# Three_Phase_Inverter.net
KiCad netlist of a schematic drawn in Altium Designer
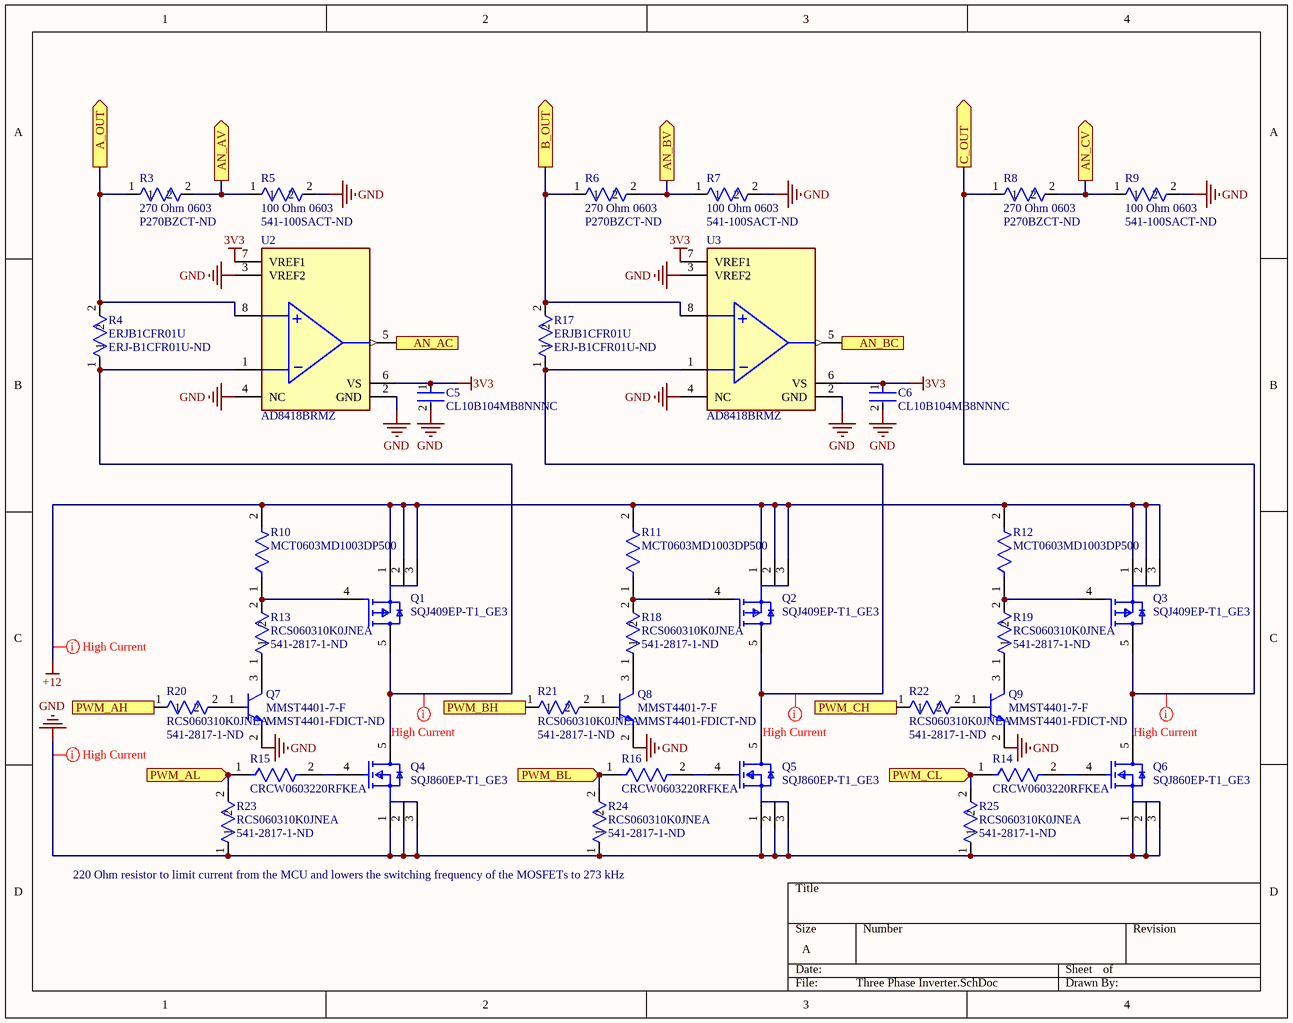
[diagram p0: Three Phase Inverter.SchDoc]

(export (version "E")
  (design (tool "Eeschema 10.0.6"))
  (components
    (comp (ref "C5")
      (value "CL10B104MB8NNNC")
      (footprint "FP-CL10-IPC_C")
      (description "Cap Ceramic 100nF 50V X7R ±20% Pad SMD 0603 +125°C T/R")
      (fields (field (name "TOLERANCE") "20%"))
      (libsource (lib "Altium Content Vault") (part "b4654b650e69147ec39a6b967a45e02"))
    )
    (comp (ref "C6")
      (value "CL10B104MB8NNNC")
      (footprint "FP-CL10-IPC_C")
      (description "Cap Ceramic 100nF 50V X7R ±20% Pad SMD 0603 +125°C T/R")
      (fields (field (name "TOLERANCE") "20%"))
      (libsource (lib "Altium Content Vault") (part "b4654b650e69147ec39a6b967a45e02"))
    )
    (comp (ref "Q1")
      (value "SQJ409EP-T1_GE3")
      (footprint "SQJ409EP-T1_GE3")
      (libsource (lib "Schematic Library") (part "SQJ409EP-T1_GE3"))
    )
    (comp (ref "Q2")
      (value "SQJ409EP-T1_GE3")
      (footprint "SQJ409EP-T1_GE3")
      (libsource (lib "Schematic Library") (part "SQJ409EP-T1_GE3"))
    )
    (comp (ref "Q3")
      (value "SQJ409EP-T1_GE3")
      (footprint "SQJ409EP-T1_GE3")
      (libsource (lib "Schematic Library") (part "SQJ409EP-T1_GE3"))
    )
    (comp (ref "Q4")
      (value "SQJ860EP-T1_GE3")
      (footprint "SQJ860EP")
      (description "RESET GENERATOR SOT23")
      (fields (field (name "MANUFACTURER") "Vishay"))
      (libsource (lib "Schematic Library") (part "SQJ860EP-T1_GE3"))
    )
    (comp (ref "Q5")
      (value "SQJ860EP-T1_GE3")
      (footprint "SQJ860EP")
      (description "RESET GENERATOR SOT23")
      (fields (field (name "MANUFACTURER") "Vishay"))
      (libsource (lib "Schematic Library") (part "SQJ860EP-T1_GE3"))
    )
    (comp (ref "Q6")
      (value "SQJ860EP-T1_GE3")
      (footprint "SQJ860EP")
      (description "RESET GENERATOR SOT23")
      (fields (field (name "MANUFACTURER") "Vishay"))
      (libsource (lib "Schematic Library") (part "SQJ860EP-T1_GE3"))
    )
    (comp (ref "Q7")
      (value "MMST4401-7-F")
      (footprint "MMST4401-7-F")
      (description "TRANS NPN 40V 0.6A SC70-3")
      (fields
        (field (name "MANUFACTURER") "Diodes")
        (field (name "SUPPLIER PART NUMBER 1") "MMST4401-FDICT-ND")
      )
      (libsource (lib "Schematic Library") (part "MMST4401-7-F"))
    )
    (comp (ref "Q8")
      (value "MMST4401-7-F")
      (footprint "MMST4401-7-F")
      (description "TRANS NPN 40V 0.6A SC70-3")
      (fields
        (field (name "MANUFACTURER") "Diodes")
        (field (name "SUPPLIER PART NUMBER 1") "MMST4401-FDICT-ND")
      )
      (libsource (lib "Schematic Library") (part "MMST4401-7-F"))
    )
    (comp (ref "Q9")
      (value "MMST4401-7-F")
      (footprint "MMST4401-7-F")
      (description "TRANS NPN 40V 0.6A SC70-3")
      (fields
        (field (name "MANUFACTURER") "Diodes")
        (field (name "SUPPLIER PART NUMBER 1") "MMST4401-FDICT-ND")
      )
      (libsource (lib "Schematic Library") (part "MMST4401-7-F"))
    )
    (comp (ref "R3")
      (value "270 Ohm 0603")
      (footprint "ERJ-PA3J271V")
      (description "Res Thick Film 0603 270 Ohm 5% 0.25W(1/4W) ±200ppm/C Pad SMD Automotive T/R")
      (fields
        (field (name "MANUFACTURER") "Panasonic")
        (field (name "MANUFACTURER PART NUMBER") "ERJ-PA3J271V")
        (field (name "SUPPLIER PART NUMBER 1") "P270BZCT-ND")
      )
      (libsource (lib "Schematic Library") (part "ERJ-PA3J271V"))
    )
    (comp (ref "R4")
      (value "ERJB1CFR01U")
      (footprint "ERJ-B1CFR01U")
      (description "Res Thick Film 1020 0.01 Ohm 1% 2W ±350ppm/°C Molded SMD Embossed Carrier T/R")
      (fields
        (field (name "MANUFACTURER") "Panasonic")
        (field (name "TOLERANCE") "1%")
        (field (name "SUPPLIER PART NUMBER 1") "ERJ-B1CFR01U-ND")
      )
      (libsource (lib "Schematic Library") (part "ERJB1CFR01U"))
    )
    (comp (ref "R5")
      (value "100 Ohm 0603")
      (footprint "CRCW0603100RJNEAHP")
      (description "Res Thick Film 0603 100 Ohm 5% 1/4W 200ppm/C Molded SMD SMD Paper T/R")
      (fields
        (field (name "MANUFACTURER") "Vishay Dale")
        (field (name "MANUFACTURER PART NUMBER") "CRCW0603100RJNEAHP")
        (field (name "SUPPLIER PART NUMBER 1") "541-100SACT-ND")
      )
      (libsource (lib "Schematic Library") (part "CRCW0603100RJNEAHP"))
    )
    (comp (ref "R6")
      (value "270 Ohm 0603")
      (footprint "ERJ-PA3J271V")
      (description "Res Thick Film 0603 270 Ohm 5% 0.25W(1/4W) ±200ppm/C Pad SMD Automotive T/R")
      (fields
        (field (name "MANUFACTURER") "Panasonic")
        (field (name "MANUFACTURER PART NUMBER") "ERJ-PA3J271V")
        (field (name "SUPPLIER PART NUMBER 1") "P270BZCT-ND")
      )
      (libsource (lib "Schematic Library") (part "ERJ-PA3J271V"))
    )
    (comp (ref "R7")
      (value "100 Ohm 0603")
      (footprint "CRCW0603100RJNEAHP")
      (description "Res Thick Film 0603 100 Ohm 5% 1/4W 200ppm/C Molded SMD SMD Paper T/R")
      (fields
        (field (name "MANUFACTURER") "Vishay Dale")
        (field (name "MANUFACTURER PART NUMBER") "CRCW0603100RJNEAHP")
        (field (name "SUPPLIER PART NUMBER 1") "541-100SACT-ND")
      )
      (libsource (lib "Schematic Library") (part "CRCW0603100RJNEAHP"))
    )
    (comp (ref "R8")
      (value "270 Ohm 0603")
      (footprint "ERJ-PA3J271V")
      (description "Res Thick Film 0603 270 Ohm 5% 0.25W(1/4W) ±200ppm/C Pad SMD Automotive T/R")
      (fields
        (field (name "MANUFACTURER") "Panasonic")
        (field (name "MANUFACTURER PART NUMBER") "ERJ-PA3J271V")
        (field (name "SUPPLIER PART NUMBER 1") "P270BZCT-ND")
      )
      (libsource (lib "Schematic Library") (part "ERJ-PA3J271V"))
    )
    (comp (ref "R9")
      (value "100 Ohm 0603")
      (footprint "CRCW0603100RJNEAHP")
      (description "Res Thick Film 0603 100 Ohm 5% 1/4W 200ppm/C Molded SMD SMD Paper T/R")
      (fields
        (field (name "MANUFACTURER") "Vishay Dale")
        (field (name "MANUFACTURER PART NUMBER") "CRCW0603100RJNEAHP")
        (field (name "SUPPLIER PART NUMBER 1") "541-100SACT-ND")
      )
      (libsource (lib "Schematic Library") (part "CRCW0603100RJNEAHP"))
    )
    (comp (ref "R10")
      (value "MCT0603MD1003DP500")
      (footprint "FP-MCT0603-IPC_A")
      (description "RES SMD 100K OHM 1% 1/8W 0603")
      (fields (field (name "TOLERANCE") "0.5%"))
      (libsource (lib "Altium Content Vault") (part "1029c3af85768c4190bb7ad29bc67b5"))
    )
    (comp (ref "R11")
      (value "MCT0603MD1003DP500")
      (footprint "FP-MCT0603-IPC_A")
      (description "RES SMD 100 OHM 1% 1/8W 0603")
      (fields (field (name "TOLERANCE") "0.5%"))
      (libsource (lib "Altium Content Vault") (part "1029c3af85768c4190bb7ad29bc67b5"))
    )
    (comp (ref "R12")
      (value "MCT0603MD1003DP500")
      (footprint "FP-MCT0603-IPC_A")
      (description "RES SMD 100 OHM 1% 1/8W 0603")
      (fields (field (name "TOLERANCE") "0.5%"))
      (libsource (lib "Altium Content Vault") (part "1029c3af85768c4190bb7ad29bc67b5"))
    )
    (comp (ref "R13")
      (value "RCS060310K0JNEA")
      (footprint "RCS060310K0JNEA")
      (description "RES SMD 10K OHM 5% 1/4W 0603")
      (fields
        (field (name "MANUFACTURER") "Vishay Dale")
        (field (name "TOLERANCE") "5%")
        (field (name "SUPPLIER PART NUMBER 1") "541-2817-1-ND")
      )
      (libsource (lib "Schematic Library") (part "RCS060310K0JNEA"))
    )
    (comp (ref "R14")
      (value "CRCW0603220RFKEA")
      (footprint "FP-CRCW0603-e3-MFG")
      (description "RES Thick Film, 220Ω, 1%, 0.1W, 100ppm/°C, 0603")
      (fields (field (name "TOLERANCE") "1%"))
      (libsource (lib "Altium Content Vault") (part "1029c3af85768c4190bb7ad29bc67b5"))
    )
    (comp (ref "R15")
      (value "CRCW0603220RFKEA")
      (footprint "FP-CRCW0603-e3-MFG")
      (description "RES Thick Film, 220Ω, 1%, 0.1W, 100ppm/°C, 0603")
      (fields (field (name "TOLERANCE") "1%"))
      (libsource (lib "Altium Content Vault") (part "1029c3af85768c4190bb7ad29bc67b5"))
    )
    (comp (ref "R16")
      (value "CRCW0603220RFKEA")
      (footprint "FP-CRCW0603-e3-MFG")
      (description "RES Thick Film, 220Ω, 1%, 0.1W, 100ppm/°C, 0603")
      (fields (field (name "TOLERANCE") "1%"))
      (libsource (lib "Altium Content Vault") (part "1029c3af85768c4190bb7ad29bc67b5"))
    )
    (comp (ref "R17")
      (value "ERJB1CFR01U")
      (footprint "ERJ-B1CFR01U")
      (description "Res Thick Film 1020 0.01 Ohm 1% 2W ±350ppm/°C Molded SMD Embossed Carrier T/R")
      (fields
        (field (name "MANUFACTURER") "Panasonic")
        (field (name "TOLERANCE") "1%")
        (field (name "SUPPLIER PART NUMBER 1") "ERJ-B1CFR01U-ND")
      )
      (libsource (lib "Schematic Library") (part "ERJB1CFR01U"))
    )
    (comp (ref "R18")
      (value "RCS060310K0JNEA")
      (footprint "RCS060310K0JNEA")
      (description "RES SMD 10K OHM 5% 1/4W 0603")
      (fields
        (field (name "MANUFACTURER") "Vishay Dale")
        (field (name "TOLERANCE") "5%")
        (field (name "SUPPLIER PART NUMBER 1") "541-2817-1-ND")
      )
      (libsource (lib "Schematic Library") (part "RCS060310K0JNEA"))
    )
    (comp (ref "R19")
      (value "RCS060310K0JNEA")
      (footprint "RCS060310K0JNEA")
      (description "RES SMD 10K OHM 5% 1/4W 0603")
      (fields
        (field (name "MANUFACTURER") "Vishay Dale")
        (field (name "TOLERANCE") "5%")
        (field (name "SUPPLIER PART NUMBER 1") "541-2817-1-ND")
      )
      (libsource (lib "Schematic Library") (part "RCS060310K0JNEA"))
    )
    (comp (ref "R20")
      (value "RCS060310K0JNEA")
      (footprint "RCS060310K0JNEA")
      (description "RES SMD 10K OHM 5% 1/4W 0603")
      (fields
        (field (name "MANUFACTURER") "Vishay Dale")
        (field (name "TOLERANCE") "5%")
        (field (name "SUPPLIER PART NUMBER 1") "541-2817-1-ND")
      )
      (libsource (lib "Schematic Library") (part "RCS060310K0JNEA"))
    )
    (comp (ref "R21")
      (value "RCS060310K0JNEA")
      (footprint "RCS060310K0JNEA")
      (description "RES SMD 10K OHM 5% 1/4W 0603")
      (fields
        (field (name "MANUFACTURER") "Vishay Dale")
        (field (name "TOLERANCE") "5%")
        (field (name "SUPPLIER PART NUMBER 1") "541-2817-1-ND")
      )
      (libsource (lib "Schematic Library") (part "RCS060310K0JNEA"))
    )
    (comp (ref "R22")
      (value "RCS060310K0JNEA")
      (footprint "RCS060310K0JNEA")
      (description "RES SMD 10K OHM 5% 1/4W 0603")
      (fields
        (field (name "MANUFACTURER") "Vishay Dale")
        (field (name "TOLERANCE") "5%")
        (field (name "SUPPLIER PART NUMBER 1") "541-2817-1-ND")
      )
      (libsource (lib "Schematic Library") (part "RCS060310K0JNEA"))
    )
    (comp (ref "R23")
      (value "RCS060310K0JNEA")
      (footprint "RCS060310K0JNEA")
      (description "RES SMD 10K OHM 5% 1/4W 0603")
      (fields
        (field (name "MANUFACTURER") "Vishay Dale")
        (field (name "TOLERANCE") "5%")
        (field (name "SUPPLIER PART NUMBER 1") "541-2817-1-ND")
      )
      (libsource (lib "Schematic Library") (part "RCS060310K0JNEA"))
    )
    (comp (ref "R24")
      (value "RCS060310K0JNEA")
      (footprint "RCS060310K0JNEA")
      (description "RES SMD 10K OHM 5% 1/4W 0603")
      (fields
        (field (name "MANUFACTURER") "Vishay Dale")
        (field (name "TOLERANCE") "5%")
        (field (name "SUPPLIER PART NUMBER 1") "541-2817-1-ND")
      )
      (libsource (lib "Schematic Library") (part "RCS060310K0JNEA"))
    )
    (comp (ref "R25")
      (value "RCS060310K0JNEA")
      (footprint "RCS060310K0JNEA")
      (description "RES SMD 10K OHM 5% 1/4W 0603")
      (fields
        (field (name "MANUFACTURER") "Vishay Dale")
        (field (name "TOLERANCE") "5%")
        (field (name "SUPPLIER PART NUMBER 1") "541-2817-1-ND")
      )
      (libsource (lib "Schematic Library") (part "RCS060310K0JNEA"))
    )
    (comp (ref "U2")
      (value "AD8418BRMZ")
      (footprint "FP-RM-8-IPC_C")
      (description "IC CURR SENSE 1 CIRCUIT 8MSOP")
      (fields
        (field (name "OCTOPART") "https://octopart.com/ad8418brmz-analog+devices-21054230")
        (field (name "MANUFACTURER") "Analog Devices")
      )
      (libsource (lib "Altium Content Vault") (part "03744de002b8bba09019ca20017b8fc"))
    )
    (comp (ref "U3")
      (value "AD8418BRMZ")
      (footprint "FP-RM-8-IPC_C")
      (description "IC CURR SENSE 1 CIRCUIT 8MSOP")
      (fields
        (field (name "OCTOPART") "https://octopart.com/ad8418brmz-analog+devices-21054230")
        (field (name "MANUFACTURER") "Analog Devices")
      )
      (libsource (lib "Altium Content Vault") (part "03744de002b8bba09019ca20017b8fc"))
    )
  )
  (nets
    (net (code "1") (name "+12") (class "Default")
      (node (ref "Q1") (pin "1") (pinfunction "S_1") (pintype "passive"))
      (node (ref "Q1") (pin "2") (pinfunction "S_2") (pintype "passive"))
      (node (ref "Q1") (pin "3") (pinfunction "S_3") (pintype "passive"))
      (node (ref "Q2") (pin "1") (pinfunction "S_1") (pintype "passive"))
      (node (ref "Q2") (pin "2") (pinfunction "S_2") (pintype "passive"))
      (node (ref "Q2") (pin "3") (pinfunction "S_3") (pintype "passive"))
      (node (ref "Q3") (pin "1") (pinfunction "S_1") (pintype "passive"))
      (node (ref "Q3") (pin "2") (pinfunction "S_2") (pintype "passive"))
      (node (ref "Q3") (pin "3") (pinfunction "S_3") (pintype "passive"))
      (node (ref "R10") (pin "2") (pinfunction "2_2") (pintype "passive"))
      (node (ref "R11") (pin "2") (pinfunction "2_2") (pintype "passive"))
      (node (ref "R12") (pin "2") (pinfunction "2_2") (pintype "passive"))
    )
    (net (code "2") (name "/AN_AC") (class "Default")
      (node (ref "U2") (pin "5") (pinfunction "OUT_5") (pintype "output"))
    )
    (net (code "3") (name "/AN_AV") (class "Default")
      (node (ref "R3") (pin "2") (pinfunction "2_2") (pintype "passive"))
      (node (ref "R5") (pin "1") (pinfunction "1_1") (pintype "passive"))
    )
    (net (code "4") (name "/AN_BC") (class "Default")
      (node (ref "U3") (pin "5") (pinfunction "OUT_5") (pintype "output"))
    )
    (net (code "5") (name "/AN_BV") (class "Default")
      (node (ref "R6") (pin "2") (pinfunction "2_2") (pintype "passive"))
      (node (ref "R7") (pin "1") (pinfunction "1_1") (pintype "passive"))
    )
    (net (code "6") (name "/AN_CV") (class "Default")
      (node (ref "R8") (pin "2") (pinfunction "2_2") (pintype "passive"))
      (node (ref "R9") (pin "1") (pinfunction "1_1") (pintype "passive"))
    )
    (net (code "7") (name "/A_OUT") (class "Default")
      (node (ref "R3") (pin "1") (pinfunction "1_1") (pintype "passive"))
      (node (ref "R4") (pin "2") (pinfunction "2_2") (pintype "passive"))
      (node (ref "U2") (pin "8") (pinfunction "+IN_8") (pintype "tri_state"))
    )
    (net (code "8") (name "/B_OUT") (class "Default")
      (node (ref "R17") (pin "2") (pinfunction "2_2") (pintype "passive"))
      (node (ref "R6") (pin "1") (pinfunction "1_1") (pintype "passive"))
      (node (ref "U3") (pin "8") (pinfunction "+IN_8") (pintype "tri_state"))
    )
    (net (code "9") (name "/C_OUT") (class "Default")
      (node (ref "Q3") (pin "5") (pinfunction "D_5") (pintype "passive"))
      (node (ref "Q6") (pin "5") (pinfunction "D_5") (pintype "passive"))
      (node (ref "R8") (pin "1") (pinfunction "1_1") (pintype "passive"))
    )
    (net (code "10") (name "/PWM_AH") (class "Default")
      (node (ref "R20") (pin "1") (pinfunction "1_1") (pintype "passive"))
    )
    (net (code "11") (name "/PWM_AL") (class "Default")
      (node (ref "R15") (pin "1") (pinfunction "1_1") (pintype "passive"))
      (node (ref "R23") (pin "2") (pinfunction "2_2") (pintype "passive"))
    )
    (net (code "12") (name "/PWM_BH") (class "Default")
      (node (ref "R21") (pin "1") (pinfunction "1_1") (pintype "passive"))
    )
    (net (code "13") (name "/PWM_BL") (class "Default")
      (node (ref "R16") (pin "1") (pinfunction "1_1") (pintype "passive"))
      (node (ref "R24") (pin "2") (pinfunction "2_2") (pintype "passive"))
    )
    (net (code "14") (name "/PWM_CH") (class "Default")
      (node (ref "R22") (pin "1") (pinfunction "1_1") (pintype "passive"))
    )
    (net (code "15") (name "/PWM_CL") (class "Default")
      (node (ref "R14") (pin "1") (pinfunction "1_1") (pintype "passive"))
      (node (ref "R25") (pin "2") (pinfunction "2_2") (pintype "passive"))
    )
    (net (code "16") (name "3V3") (class "Default")
      (node (ref "C5") (pin "1") (pinfunction "1_1") (pintype "passive"))
      (node (ref "C6") (pin "1") (pinfunction "1_1") (pintype "passive"))
      (node (ref "U2") (pin "6") (pinfunction "VS_6") (pintype "power_in"))
      (node (ref "U2") (pin "7") (pinfunction "VREF1_7") (pintype "power_in"))
      (node (ref "U3") (pin "6") (pinfunction "VS_6") (pintype "power_in"))
      (node (ref "U3") (pin "7") (pinfunction "VREF1_7") (pintype "power_in"))
    )
    (net (code "17") (name "GND") (class "Default")
      (node (ref "C5") (pin "2") (pinfunction "2_2") (pintype "passive"))
      (node (ref "C6") (pin "2") (pinfunction "2_2") (pintype "passive"))
      (node (ref "Q4") (pin "1") (pinfunction "S_1") (pintype "passive"))
      (node (ref "Q4") (pin "2") (pinfunction "S_2") (pintype "passive"))
      (node (ref "Q4") (pin "3") (pinfunction "S_3") (pintype "passive"))
      (node (ref "Q5") (pin "1") (pinfunction "S_1") (pintype "passive"))
      (node (ref "Q5") (pin "2") (pinfunction "S_2") (pintype "passive"))
      (node (ref "Q5") (pin "3") (pinfunction "S_3") (pintype "passive"))
      (node (ref "Q6") (pin "1") (pinfunction "S_1") (pintype "passive"))
      (node (ref "Q6") (pin "2") (pinfunction "S_2") (pintype "passive"))
      (node (ref "Q6") (pin "3") (pinfunction "S_3") (pintype "passive"))
      (node (ref "Q7") (pin "2") (pinfunction "E_2") (pintype "passive"))
      (node (ref "Q8") (pin "2") (pinfunction "E_2") (pintype "passive"))
      (node (ref "Q9") (pin "2") (pinfunction "E_2") (pintype "passive"))
      (node (ref "R23") (pin "1") (pinfunction "1_1") (pintype "passive"))
      (node (ref "R24") (pin "1") (pinfunction "1_1") (pintype "passive"))
      (node (ref "R25") (pin "1") (pinfunction "1_1") (pintype "passive"))
      (node (ref "R5") (pin "2") (pinfunction "2_2") (pintype "passive"))
      (node (ref "R7") (pin "2") (pinfunction "2_2") (pintype "passive"))
      (node (ref "R9") (pin "2") (pinfunction "2_2") (pintype "passive"))
      (node (ref "U2") (pin "2") (pinfunction "GND_2") (pintype "power_in"))
      (node (ref "U2") (pin "3") (pinfunction "VREF2_3") (pintype "power_in"))
      (node (ref "U2") (pin "4") (pinfunction "NC_4") (pintype "passive"))
      (node (ref "U3") (pin "2") (pinfunction "GND_2") (pintype "power_in"))
      (node (ref "U3") (pin "3") (pinfunction "VREF2_3") (pintype "power_in"))
      (node (ref "U3") (pin "4") (pinfunction "NC_4") (pintype "passive"))
    )
    (net (code "18") (name "Net-(Q1-D)") (class "Default")
      (node (ref "Q1") (pin "5") (pinfunction "D_5") (pintype "passive"))
      (node (ref "Q4") (pin "5") (pinfunction "D_5") (pintype "passive"))
      (node (ref "R4") (pin "1") (pinfunction "1_1") (pintype "passive"))
      (node (ref "U2") (pin "1") (pinfunction "-IN_1") (pintype "tri_state"))
    )
    (net (code "19") (name "Net-(Q1-G)") (class "Default")
      (node (ref "Q1") (pin "4") (pinfunction "G_4") (pintype "passive"))
      (node (ref "R10") (pin "1") (pinfunction "1_1") (pintype "passive"))
      (node (ref "R13") (pin "2") (pinfunction "2_2") (pintype "passive"))
    )
    (net (code "20") (name "Net-(Q2-D)") (class "Default")
      (node (ref "Q2") (pin "5") (pinfunction "D_5") (pintype "passive"))
      (node (ref "Q5") (pin "5") (pinfunction "D_5") (pintype "passive"))
      (node (ref "R17") (pin "1") (pinfunction "1_1") (pintype "passive"))
      (node (ref "U3") (pin "1") (pinfunction "-IN_1") (pintype "tri_state"))
    )
    (net (code "21") (name "Net-(Q2-G)") (class "Default")
      (node (ref "Q2") (pin "4") (pinfunction "G_4") (pintype "passive"))
      (node (ref "R11") (pin "1") (pinfunction "1_1") (pintype "passive"))
      (node (ref "R18") (pin "2") (pinfunction "2_2") (pintype "passive"))
    )
    (net (code "22") (name "Net-(Q3-G)") (class "Default")
      (node (ref "Q3") (pin "4") (pinfunction "G_4") (pintype "passive"))
      (node (ref "R12") (pin "1") (pinfunction "1_1") (pintype "passive"))
      (node (ref "R19") (pin "2") (pinfunction "2_2") (pintype "passive"))
    )
    (net (code "23") (name "Net-(Q4-G)") (class "Default")
      (node (ref "Q4") (pin "4") (pinfunction "G_4") (pintype "passive"))
      (node (ref "R15") (pin "2") (pinfunction "2_2") (pintype "passive"))
    )
    (net (code "24") (name "Net-(Q5-G)") (class "Default")
      (node (ref "Q5") (pin "4") (pinfunction "G_4") (pintype "passive"))
      (node (ref "R16") (pin "2") (pinfunction "2_2") (pintype "passive"))
    )
    (net (code "25") (name "Net-(Q6-G)") (class "Default")
      (node (ref "Q6") (pin "4") (pinfunction "G_4") (pintype "passive"))
      (node (ref "R14") (pin "2") (pinfunction "2_2") (pintype "passive"))
    )
    (net (code "26") (name "Net-(Q7-B)") (class "Default")
      (node (ref "Q7") (pin "1") (pinfunction "B_1") (pintype "passive"))
      (node (ref "R20") (pin "2") (pinfunction "2_2") (pintype "passive"))
    )
    (net (code "27") (name "Net-(Q7-C)") (class "Default")
      (node (ref "Q7") (pin "3") (pinfunction "C_3") (pintype "passive"))
      (node (ref "R13") (pin "1") (pinfunction "1_1") (pintype "passive"))
    )
    (net (code "28") (name "Net-(Q8-B)") (class "Default")
      (node (ref "Q8") (pin "1") (pinfunction "B_1") (pintype "passive"))
      (node (ref "R21") (pin "2") (pinfunction "2_2") (pintype "passive"))
    )
    (net (code "29") (name "Net-(Q8-C)") (class "Default")
      (node (ref "Q8") (pin "3") (pinfunction "C_3") (pintype "passive"))
      (node (ref "R18") (pin "1") (pinfunction "1_1") (pintype "passive"))
    )
    (net (code "30") (name "Net-(Q9-B)") (class "Default")
      (node (ref "Q9") (pin "1") (pinfunction "B_1") (pintype "passive"))
      (node (ref "R22") (pin "2") (pinfunction "2_2") (pintype "passive"))
    )
    (net (code "31") (name "Net-(Q9-C)") (class "Default")
      (node (ref "Q9") (pin "3") (pinfunction "C_3") (pintype "passive"))
      (node (ref "R19") (pin "1") (pinfunction "1_1") (pintype "passive"))
    )
  )
)
